# labproject_1_pcb.net
KiCad netlist of a schematic drawn in Altium Designer
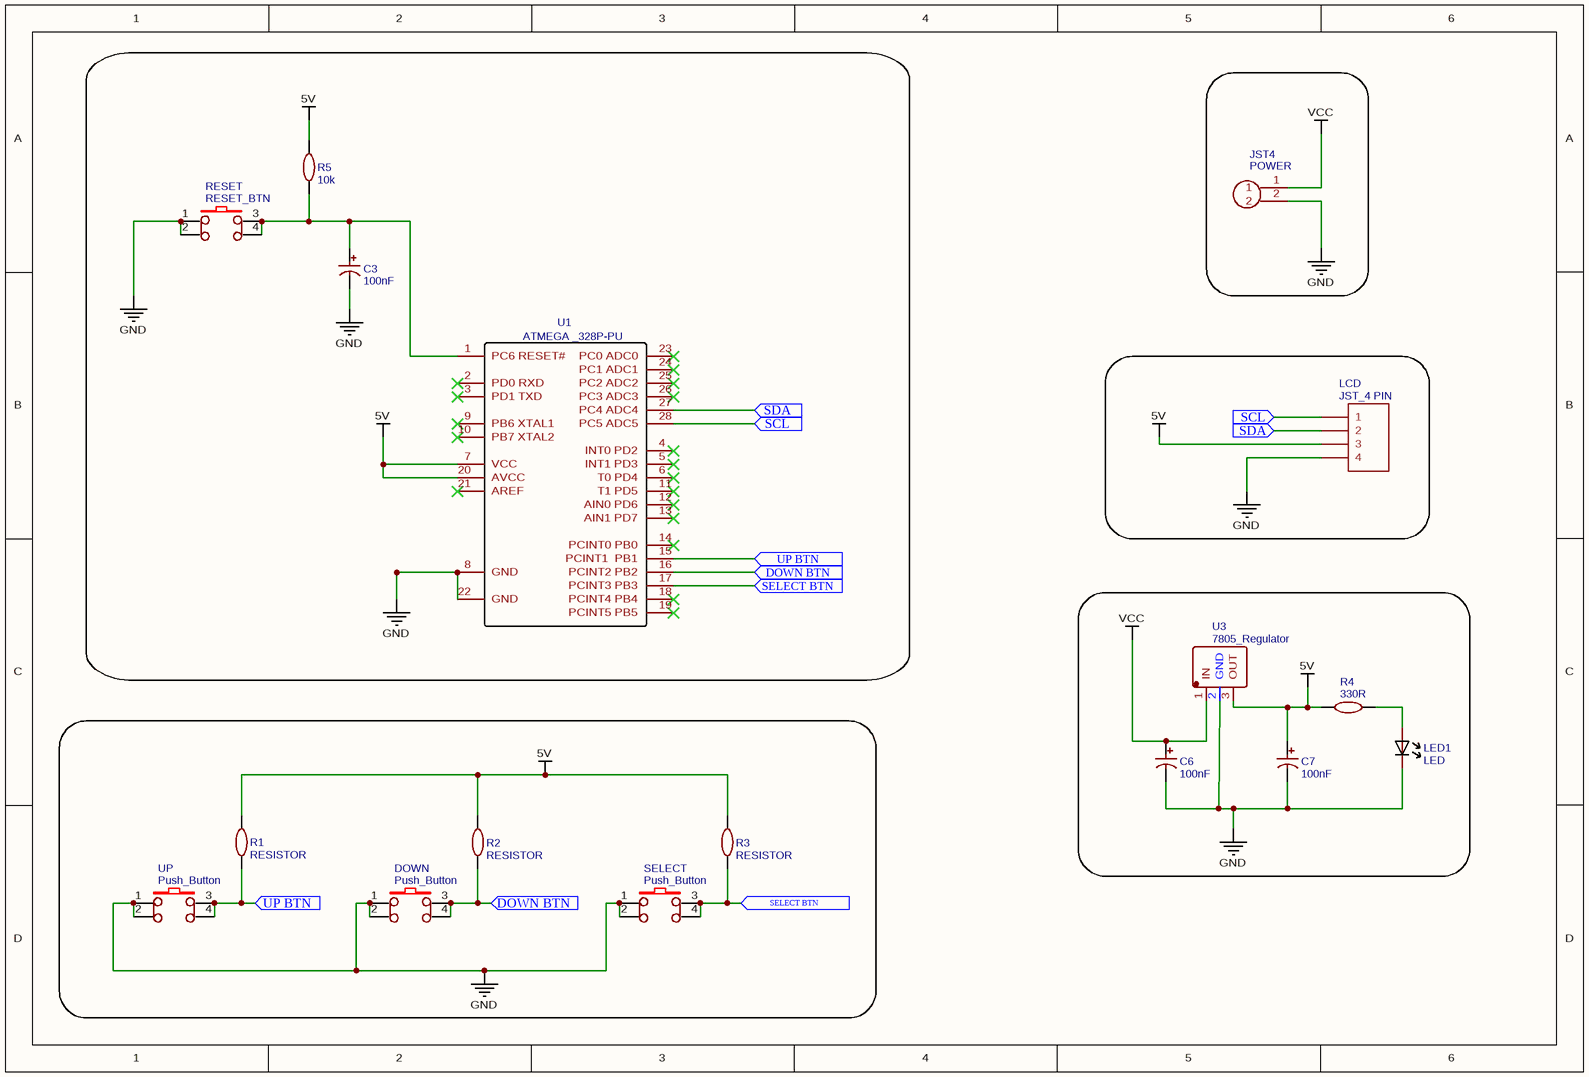
[diagram p0: labproject_1_pcb.schdoc]

(export (version "E")
  (design (tool "Eeschema 10.0.6"))
  (components
    (comp (ref "C3")
      (value "100nF")
      (footprint "CAP-TH_BD5.0-P2.00-D0.8-FD")
      (fields (field (name "BOM_MANUFACTURER PART") "0.1UF 50V") (field (name "BOM_SUPPLIER PART") "C28061"))
      (libsource (lib "altium-import") (part "root_0_100nF_"))
    )
    (comp (ref "C6")
      (value "100nF")
      (footprint "CAP-TH_BD5.0-P2.00-D0.8-FD")
      (fields (field (name "BOM_MANUFACTURER PART") "0.1UF 50V") (field (name "BOM_SUPPLIER PART") "C28061"))
      (libsource (lib "altium-import") (part "root_0_100nF_"))
    )
    (comp (ref "C7")
      (value "100nF")
      (footprint "CAP-TH_BD5.0-P2.00-D0.8-FD")
      (fields (field (name "BOM_MANUFACTURER PART") "0.1UF 50V") (field (name "BOM_SUPPLIER PART") "C28061"))
      (libsource (lib "altium-import") (part "root_0_100nF_"))
    )
    (comp (ref "DOWN")
      (value "Push_Button")
      (footprint "KEY-TH_4P-L6.0-W6.0-P4.50")
      (fields
        (field (name "BOM_SUPPLIER PART") "C59980")
        (field (name "BOM_MANUFACTURER PART") "button6*6*8.5")
      )
      (libsource (lib "altium-import") (part "root_0_Push_Button_"))
    )
    (comp (ref "JST4")
      (value "POWER")
      (footprint "CONN-TH_XHB-2A")
      (fields
        (field (name "BOM_MANUFACTURER PART") "XHB-2A Connector")
        (field (name "BOM_SUPPLIER PART") "C57981")
      )
      (libsource (lib "altium-import") (part "root_0_POWER_"))
    )
    (comp (ref "LCD")
      (value "JST_4 PIN")
      (footprint "JST_XH_4_PIN_TOP_ENTRY")
      (fields (field (name "CONTRIBUTOR") "fabiano.riccardi"))
      (libsource (lib "altium-import") (part "root_0_JST_4 PIN_"))
    )
    (comp (ref "LED1")
      (value "LED")
      (footprint "5MM LED")
      (fields (field (name "BOM_MANUFACTURER PART") "5mm LED") (field (name "CONTRIBUTOR") "Axbri"))
      (libsource (lib "altium-import") (part "root_3_LED_"))
    )
    (comp (ref "R1")
      (value "RESISTOR")
      (footprint "AXIAL-0.4")
      (fields
        (field (name "POWER") "1/4W")
        (field (name "TOLERANCE") "±1%")
        (field (name "BOM_SUPPLIER PART") "E57439")
      )
      (libsource (lib "altium-import") (part "root_1_RESISTOR_"))
    )
    (comp (ref "R2")
      (value "RESISTOR")
      (footprint "AXIAL-0.4")
      (fields
        (field (name "POWER") "1/4W")
        (field (name "TOLERANCE") "±1%")
        (field (name "BOM_SUPPLIER PART") "E57439")
      )
      (libsource (lib "altium-import") (part "root_1_RESISTOR_"))
    )
    (comp (ref "R3")
      (value "RESISTOR")
      (footprint "AXIAL-0.4")
      (fields
        (field (name "POWER") "1/4W")
        (field (name "TOLERANCE") "±1%")
        (field (name "BOM_SUPPLIER PART") "E57439")
      )
      (libsource (lib "altium-import") (part "root_1_RESISTOR_"))
    )
    (comp (ref "R4")
      (value "330R")
      (footprint "AXIAL-0.4")
      (fields
        (field (name "POWER") "1/4W")
        (field (name "TOLERANCE") "±1%")
        (field (name "BOM_SUPPLIER PART") "E57439")
      )
      (libsource (lib "altium-import") (part "root_0_330R_"))
    )
    (comp (ref "R5")
      (value "10k")
      (footprint "AXIAL-0.4")
      (fields
        (field (name "POWER") "1/4W")
        (field (name "TOLERANCE") "±1%")
        (field (name "BOM_SUPPLIER PART") "E57439")
      )
      (libsource (lib "altium-import") (part "root_1_10k_"))
    )
    (comp (ref "RESET")
      (value "RESET_BTN")
      (footprint "KEY-TH_4P-L6.0-W6.0-P4.50")
      (fields
        (field (name "BOM_SUPPLIER PART") "C59980")
        (field (name "BOM_MANUFACTURER PART") "button6*6*8.5")
      )
      (libsource (lib "altium-import") (part "root_0_RESET_BTN_"))
    )
    (comp (ref "SELECT")
      (value "Push_Button")
      (footprint "KEY-TH_4P-L6.0-W6.0-P4.50")
      (fields
        (field (name "BOM_SUPPLIER PART") "C59980")
        (field (name "BOM_MANUFACTURER PART") "button6*6*8.5")
      )
      (libsource (lib "altium-import") (part "root_0_Push_Button_"))
    )
    (comp (ref "U1")
      (value "ATMEGA _328P-PU")
      (footprint "DIP-28_L34.6-W7.3-P2.54-LS10.2-BL")
      (fields
        (field (name "BOM_MANUFACTURER PART") "ATMEGA328P-PU")
        (field (name "BOM_SUPPLIER PART") "C33901")
        (field (name "CONTRIBUTOR") "LCSC")
      )
      (libsource (lib "altium-import") (part "root_0_ATMEGA _328P-PU_"))
    )
    (comp (ref "U3")
      (value "7805_Regulator")
      (footprint "TO-220-3_L10.0-W4.5-P2.54-L")
      (fields
        (field (name "BOM_SUPPLIER PART") "C305416")
        (field (name "BOM_MANUFACTURER PART") "7805")
        (field (name "CONTRIBUTOR") "LCSC")
      )
      (libsource (lib "altium-import") (part "root_1_7805_Regulator_"))
    )
    (comp (ref "UP")
      (value "Push_Button")
      (footprint "KEY-TH_4P-L6.0-W6.0-P4.50")
      (fields
        (field (name "BOM_SUPPLIER PART") "C59980")
        (field (name "BOM_MANUFACTURER PART") "button6*6*8.5")
      )
      (libsource (lib "altium-import") (part "root_0_Push_Button_"))
    )
  )
  (nets
    (net (code "1") (name "/DOWN BTN") (class "Default")
      (node (ref "DOWN") (pin "3") (pinfunction "3_3") (pintype "passive"))
      (node (ref "DOWN") (pin "4") (pinfunction "4_4") (pintype "passive"))
      (node (ref "R2") (pin "1") (pinfunction "1_1") (pintype "passive"))
      (node (ref "U1") (pin "16") (pinfunction "PCINT2_PB2_16") (pintype "passive"))
    )
    (net (code "2") (name "/SCL") (class "Default")
      (node (ref "LCD") (pin "1") (pinfunction "1_1") (pintype "passive"))
      (node (ref "U1") (pin "28") (pinfunction "PC5_ADC5_28") (pintype "passive"))
    )
    (net (code "3") (name "/SDA") (class "Default")
      (node (ref "LCD") (pin "2") (pinfunction "2_2") (pintype "passive"))
      (node (ref "U1") (pin "27") (pinfunction "PC4_ADC4_27") (pintype "passive"))
    )
    (net (code "4") (name "/SELECT BTN") (class "Default")
      (node (ref "R3") (pin "1") (pinfunction "1_1") (pintype "passive"))
      (node (ref "SELECT") (pin "3") (pinfunction "3_3") (pintype "passive"))
      (node (ref "SELECT") (pin "4") (pinfunction "4_4") (pintype "passive"))
      (node (ref "U1") (pin "17") (pinfunction "PCINT3_PB3_17") (pintype "passive"))
    )
    (net (code "5") (name "/UP BTN") (class "Default")
      (node (ref "R1") (pin "1") (pinfunction "1_1") (pintype "passive"))
      (node (ref "U1") (pin "15") (pinfunction "PCINT1__PB1_15") (pintype "passive"))
      (node (ref "UP") (pin "3") (pinfunction "3_3") (pintype "passive"))
      (node (ref "UP") (pin "4") (pinfunction "4_4") (pintype "passive"))
    )
    (net (code "6") (name "5V") (class "Default")
      (node (ref "C7") (pin "1") (pinfunction "1_1") (pintype "passive"))
      (node (ref "LCD") (pin "3") (pinfunction "3_3") (pintype "passive"))
      (node (ref "R1") (pin "2") (pinfunction "2_2") (pintype "passive"))
      (node (ref "R2") (pin "2") (pinfunction "2_2") (pintype "passive"))
      (node (ref "R3") (pin "2") (pinfunction "2_2") (pintype "passive"))
      (node (ref "R4") (pin "1") (pinfunction "1_1") (pintype "passive"))
      (node (ref "R5") (pin "2") (pinfunction "2_2") (pintype "passive"))
      (node (ref "U1") (pin "20") (pinfunction "AVCC_20") (pintype "passive"))
      (node (ref "U1") (pin "7") (pinfunction "VCC_7") (pintype "passive"))
      (node (ref "U3") (pin "3") (pinfunction "OUT_3") (pintype "passive"))
    )
    (net (code "7") (name "GND") (class "Default")
      (node (ref "C3") (pin "2") (pinfunction "2_2") (pintype "passive"))
      (node (ref "C6") (pin "2") (pinfunction "2_2") (pintype "passive"))
      (node (ref "C7") (pin "2") (pinfunction "2_2") (pintype "passive"))
      (node (ref "DOWN") (pin "1") (pinfunction "1_1") (pintype "passive"))
      (node (ref "DOWN") (pin "2") (pinfunction "2_2") (pintype "passive"))
      (node (ref "JST4") (pin "2") (pinfunction "2_2") (pintype "passive"))
      (node (ref "LCD") (pin "4") (pinfunction "4_4") (pintype "passive"))
      (node (ref "LED1") (pin "2") (pinfunction "2_2") (pintype "passive"))
      (node (ref "RESET") (pin "1") (pinfunction "1_1") (pintype "passive"))
      (node (ref "RESET") (pin "2") (pinfunction "2_2") (pintype "passive"))
      (node (ref "SELECT") (pin "1") (pinfunction "1_1") (pintype "passive"))
      (node (ref "SELECT") (pin "2") (pinfunction "2_2") (pintype "passive"))
      (node (ref "U1") (pin "22") (pinfunction "GND_22") (pintype "passive"))
      (node (ref "U1") (pin "8") (pinfunction "GND_8") (pintype "passive"))
      (node (ref "U3") (pin "2") (pinfunction "GND_2") (pintype "passive"))
      (node (ref "UP") (pin "1") (pinfunction "1_1") (pintype "passive"))
      (node (ref "UP") (pin "2") (pinfunction "2_2") (pintype "passive"))
    )
    (net (code "8") (name "Net-(LED1-Pad1)") (class "Default")
      (node (ref "LED1") (pin "1") (pinfunction "1_1") (pintype "passive"))
      (node (ref "R4") (pin "2") (pinfunction "2_2") (pintype "passive"))
    )
    (net (code "9") (name "Net-(U1-PC6_RESET#)") (class "Default")
      (node (ref "C3") (pin "1") (pinfunction "1_1") (pintype "passive"))
      (node (ref "R5") (pin "1") (pinfunction "1_1") (pintype "passive"))
      (node (ref "RESET") (pin "3") (pinfunction "3_3") (pintype "passive"))
      (node (ref "RESET") (pin "4") (pinfunction "4_4") (pintype "passive"))
      (node (ref "U1") (pin "1") (pinfunction "PC6_RESET#_1") (pintype "passive"))
    )
    (net (code "10") (name "VCC") (class "Default")
      (node (ref "C6") (pin "1") (pinfunction "1_1") (pintype "passive"))
      (node (ref "JST4") (pin "1") (pinfunction "1_1") (pintype "passive"))
      (node (ref "U3") (pin "1") (pinfunction "IN_1") (pintype "passive"))
    )
    (net (code "11") (name "unconnected-(U1-AIN0_PD6-Pad12)") (class "Default")
      (node (ref "U1") (pin "12") (pinfunction "AIN0_PD6_12") (pintype "passive+no_connect"))
    )
    (net (code "12") (name "unconnected-(U1-AIN1_PD7-Pad13)") (class "Default")
      (node (ref "U1") (pin "13") (pinfunction "AIN1_PD7_13") (pintype "passive+no_connect"))
    )
    (net (code "13") (name "unconnected-(U1-AREF-Pad21)") (class "Default")
      (node (ref "U1") (pin "21") (pinfunction "AREF_21") (pintype "passive+no_connect"))
    )
    (net (code "14") (name "unconnected-(U1-INT0_PD2-Pad4)") (class "Default")
      (node (ref "U1") (pin "4") (pinfunction "INT0_PD2_4") (pintype "passive+no_connect"))
    )
    (net (code "15") (name "unconnected-(U1-INT1_PD3-Pad5)") (class "Default")
      (node (ref "U1") (pin "5") (pinfunction "INT1_PD3_5") (pintype "passive+no_connect"))
    )
    (net (code "16") (name "unconnected-(U1-PB6_XTAL1-Pad9)") (class "Default")
      (node (ref "U1") (pin "9") (pinfunction "PB6_XTAL1_9") (pintype "passive+no_connect"))
    )
    (net (code "17") (name "unconnected-(U1-PB7_XTAL2-Pad10)") (class "Default")
      (node (ref "U1") (pin "10") (pinfunction "PB7_XTAL2_10") (pintype "passive+no_connect"))
    )
    (net (code "18") (name "unconnected-(U1-PC0_ADC0-Pad23)") (class "Default")
      (node (ref "U1") (pin "23") (pinfunction "PC0_ADC0_23") (pintype "passive+no_connect"))
    )
    (net (code "19") (name "unconnected-(U1-PC1_ADC1-Pad24)") (class "Default")
      (node (ref "U1") (pin "24") (pinfunction "PC1_ADC1_24") (pintype "passive+no_connect"))
    )
    (net (code "20") (name "unconnected-(U1-PC2_ADC2-Pad25)") (class "Default")
      (node (ref "U1") (pin "25") (pinfunction "PC2_ADC2_25") (pintype "passive+no_connect"))
    )
    (net (code "21") (name "unconnected-(U1-PC3_ADC3-Pad26)") (class "Default")
      (node (ref "U1") (pin "26") (pinfunction "PC3_ADC3_26") (pintype "passive+no_connect"))
    )
    (net (code "22") (name "unconnected-(U1-PCINT0_PB0-Pad14)") (class "Default")
      (node (ref "U1") (pin "14") (pinfunction "PCINT0_PB0_14") (pintype "passive+no_connect"))
    )
    (net (code "23") (name "unconnected-(U1-PCINT4_PB4-Pad18)") (class "Default")
      (node (ref "U1") (pin "18") (pinfunction "PCINT4_PB4_18") (pintype "passive+no_connect"))
    )
    (net (code "24") (name "unconnected-(U1-PCINT5_PB5-Pad19)") (class "Default")
      (node (ref "U1") (pin "19") (pinfunction "PCINT5_PB5_19") (pintype "passive+no_connect"))
    )
    (net (code "25") (name "unconnected-(U1-PD0_RXD-Pad2)") (class "Default")
      (node (ref "U1") (pin "2") (pinfunction "PD0_RXD_2") (pintype "passive+no_connect"))
    )
    (net (code "26") (name "unconnected-(U1-PD1_TXD-Pad3)") (class "Default")
      (node (ref "U1") (pin "3") (pinfunction "PD1_TXD_3") (pintype "passive+no_connect"))
    )
    (net (code "27") (name "unconnected-(U1-T0_PD4-Pad6)") (class "Default")
      (node (ref "U1") (pin "6") (pinfunction "T0_PD4_6") (pintype "passive+no_connect"))
    )
    (net (code "28") (name "unconnected-(U1-T1_PD5-Pad11)") (class "Default")
      (node (ref "U1") (pin "11") (pinfunction "T1_PD5_11") (pintype "passive+no_connect"))
    )
  )
)
